# MUX_1_1.net
KiCad netlist of a schematic drawn in EAGLE
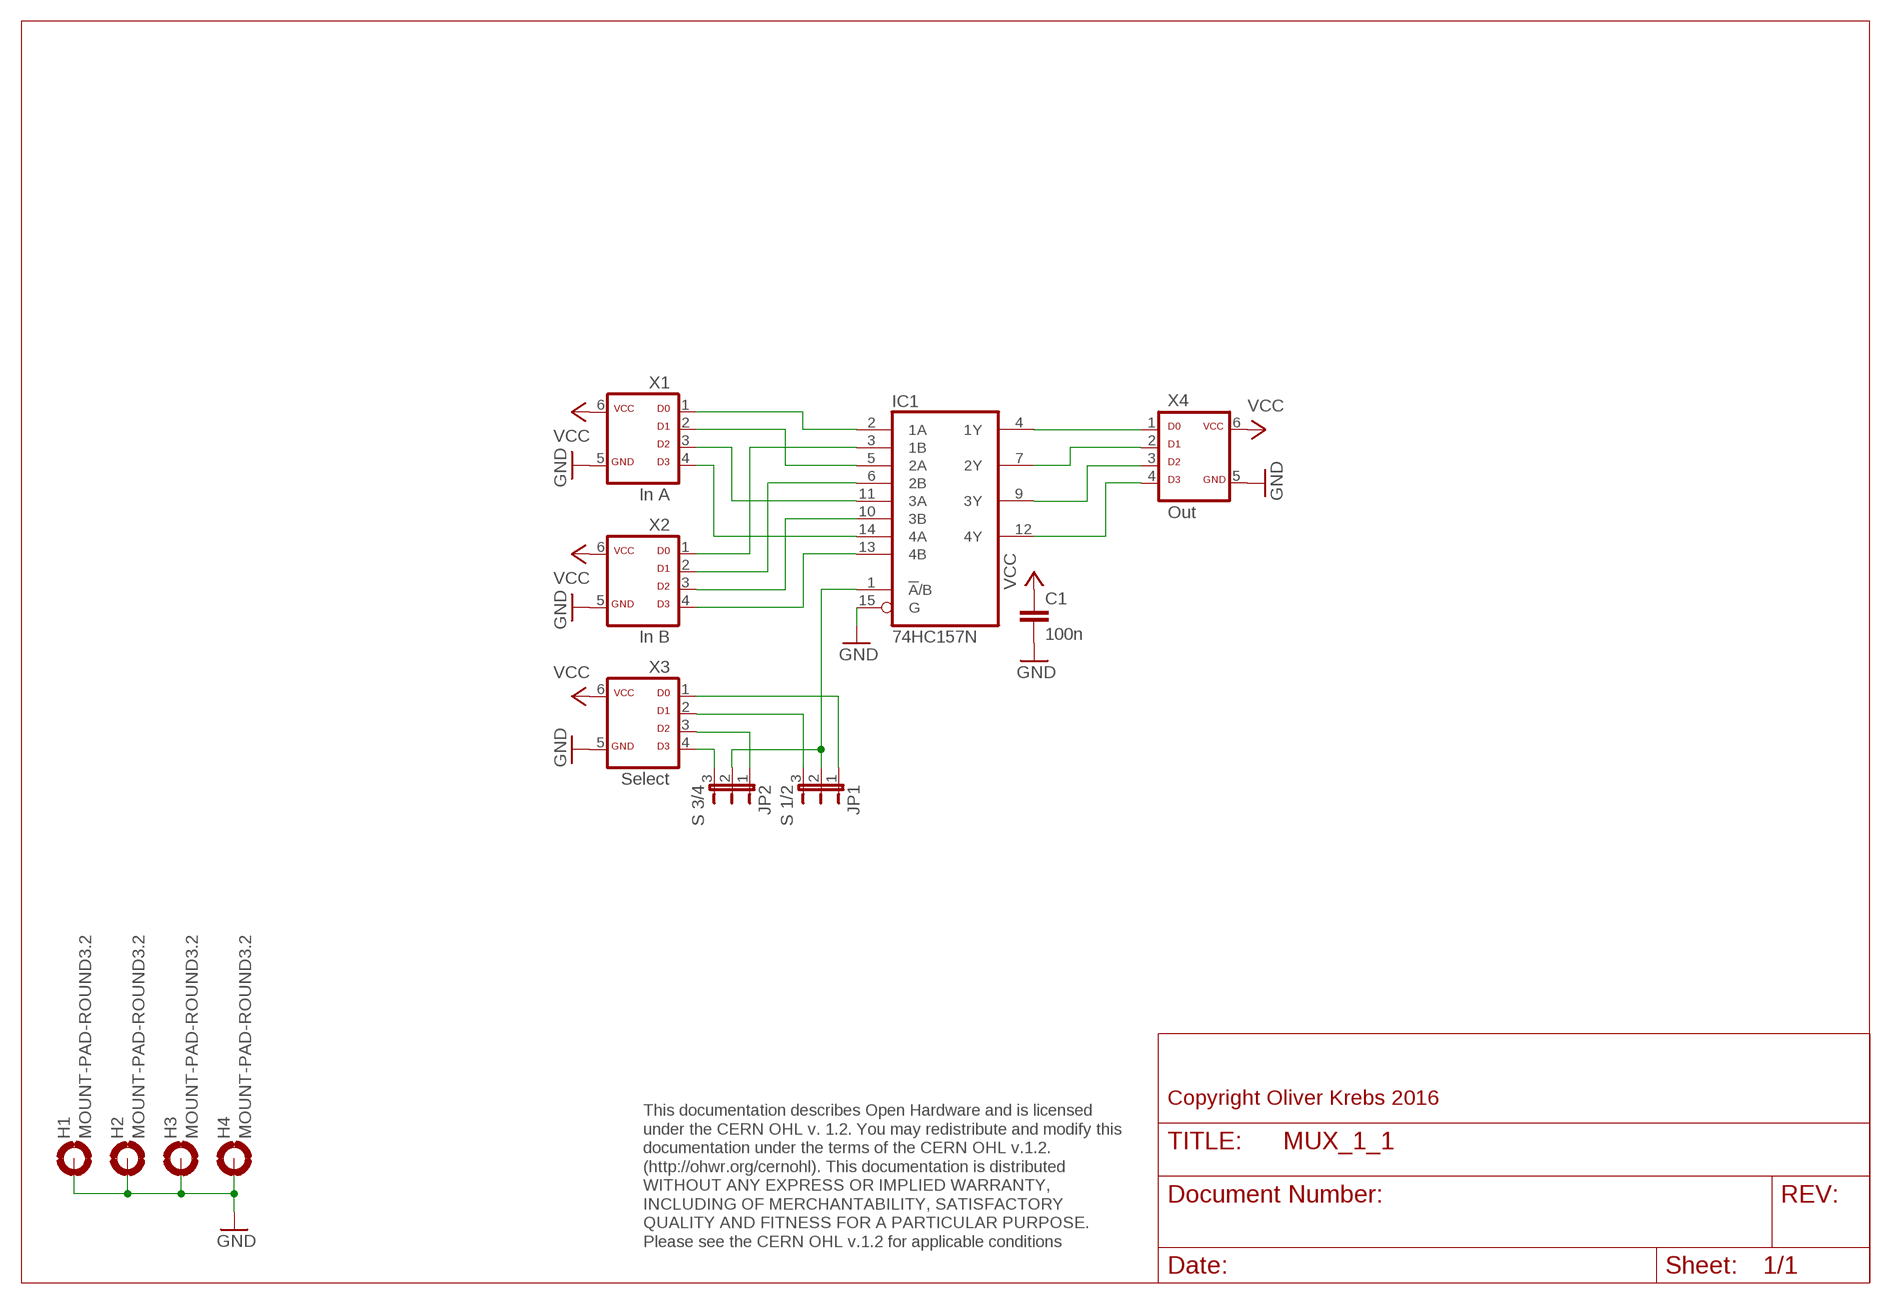
[diagram p0: schematic, sheet 1]

(export (version "E")
  (design (tool "Eeschema 10.0.6"))
  (components
    (comp (ref "C1")
      (value "100n")
      (footprint "eagle-import:C050-025X075")
      (libsource (lib "eagle-import") (part "C-EU050-025X075"))
    )
    (comp (ref "H1")
      (value "MOUNT-PAD-ROUND3.2")
      (footprint "eagle-import:3,2-PAD")
      (libsource (lib "eagle-import") (part "MOUNT-PAD-ROUND3.2"))
    )
    (comp (ref "H2")
      (value "MOUNT-PAD-ROUND3.2")
      (footprint "eagle-import:3,2-PAD")
      (libsource (lib "eagle-import") (part "MOUNT-PAD-ROUND3.2"))
    )
    (comp (ref "H3")
      (value "MOUNT-PAD-ROUND3.2")
      (footprint "eagle-import:3,2-PAD")
      (libsource (lib "eagle-import") (part "MOUNT-PAD-ROUND3.2"))
    )
    (comp (ref "H4")
      (value "MOUNT-PAD-ROUND3.2")
      (footprint "eagle-import:3,2-PAD")
      (libsource (lib "eagle-import") (part "MOUNT-PAD-ROUND3.2"))
    )
    (comp (ref "IC1")
      (value "74HC157N")
      (footprint "eagle-import:DIL16")
      (libsource (lib "eagle-import") (part "74157NHC"))
    )
    (comp (ref "JP1")
      (value "S 1/2")
      (footprint "eagle-import:JP2")
      (libsource (lib "eagle-import") (part "JP2E"))
    )
    (comp (ref "JP2")
      (value "S 3/4")
      (footprint "eagle-import:JP2")
      (libsource (lib "eagle-import") (part "JP2E"))
    )
    (comp (ref "X1")
      (value "In A")
      (footprint "eagle-import:ML-6")
      (libsource (lib "eagle-import") (part "ML6D"))
    )
    (comp (ref "X2")
      (value "In B")
      (footprint "eagle-import:ML-6")
      (libsource (lib "eagle-import") (part "ML6D"))
    )
    (comp (ref "X3")
      (value "Select")
      (footprint "eagle-import:ML-6")
      (libsource (lib "eagle-import") (part "ML6D"))
    )
    (comp (ref "X4")
      (value "Out")
      (footprint "eagle-import:ML-6")
      (libsource (lib "eagle-import") (part "ML6D"))
    )
  )
  (nets
    (net (code "1") (name "GND") (class "Default")
      (node (ref "C1") (pin "2") (pinfunction "2_2") (pintype "passive"))
      (node (ref "H1") (pin "B3,2") (pinfunction "MOUNT_B3,2") (pintype "passive"))
      (node (ref "H2") (pin "B3,2") (pinfunction "MOUNT_B3,2") (pintype "passive"))
      (node (ref "H3") (pin "B3,2") (pinfunction "MOUNT_B3,2") (pintype "passive"))
      (node (ref "H4") (pin "B3,2") (pinfunction "MOUNT_B3,2") (pintype "passive"))
      (node (ref "IC1") (pin "15") (pinfunction "G_15") (pintype "input"))
      (node (ref "X1") (pin "5") (pinfunction "5_5") (pintype "passive"))
      (node (ref "X2") (pin "5") (pinfunction "5_5") (pintype "passive"))
      (node (ref "X3") (pin "5") (pinfunction "5_5") (pintype "passive"))
      (node (ref "X4") (pin "5") (pinfunction "5_5") (pintype "passive"))
    )
    (net (code "2") (name "Net-(IC1A-1A)") (class "Default")
      (node (ref "IC1") (pin "2") (pinfunction "1A_2") (pintype "input"))
      (node (ref "X1") (pin "1") (pinfunction "1_1") (pintype "passive"))
    )
    (net (code "3") (name "Net-(IC1A-1B)") (class "Default")
      (node (ref "IC1") (pin "3") (pinfunction "1B_3") (pintype "input"))
      (node (ref "X2") (pin "1") (pinfunction "1_1") (pintype "passive"))
    )
    (net (code "4") (name "Net-(IC1A-1Y)") (class "Default")
      (node (ref "IC1") (pin "4") (pinfunction "1Y_4") (pintype "output"))
      (node (ref "X4") (pin "1") (pinfunction "1_1") (pintype "passive"))
    )
    (net (code "5") (name "Net-(IC1A-2A)") (class "Default")
      (node (ref "IC1") (pin "5") (pinfunction "2A_5") (pintype "input"))
      (node (ref "X1") (pin "2") (pinfunction "2_2") (pintype "passive"))
    )
    (net (code "6") (name "Net-(IC1A-2B)") (class "Default")
      (node (ref "IC1") (pin "6") (pinfunction "2B_6") (pintype "input"))
      (node (ref "X2") (pin "2") (pinfunction "2_2") (pintype "passive"))
    )
    (net (code "7") (name "Net-(IC1A-2Y)") (class "Default")
      (node (ref "IC1") (pin "7") (pinfunction "2Y_7") (pintype "output"))
      (node (ref "X4") (pin "2") (pinfunction "2_2") (pintype "passive"))
    )
    (net (code "8") (name "Net-(IC1A-3A)") (class "Default")
      (node (ref "IC1") (pin "11") (pinfunction "3A_11") (pintype "input"))
      (node (ref "X1") (pin "3") (pinfunction "3_3") (pintype "passive"))
    )
    (net (code "9") (name "Net-(IC1A-3B)") (class "Default")
      (node (ref "IC1") (pin "10") (pinfunction "3B_10") (pintype "input"))
      (node (ref "X2") (pin "3") (pinfunction "3_3") (pintype "passive"))
    )
    (net (code "10") (name "Net-(IC1A-3Y)") (class "Default")
      (node (ref "IC1") (pin "9") (pinfunction "3Y_9") (pintype "output"))
      (node (ref "X4") (pin "3") (pinfunction "3_3") (pintype "passive"))
    )
    (net (code "11") (name "Net-(IC1A-4A)") (class "Default")
      (node (ref "IC1") (pin "14") (pinfunction "4A_14") (pintype "input"))
      (node (ref "X1") (pin "4") (pinfunction "4_4") (pintype "passive"))
    )
    (net (code "12") (name "Net-(IC1A-4B)") (class "Default")
      (node (ref "IC1") (pin "13") (pinfunction "4B_13") (pintype "input"))
      (node (ref "X2") (pin "4") (pinfunction "4_4") (pintype "passive"))
    )
    (net (code "13") (name "Net-(IC1A-4Y)") (class "Default")
      (node (ref "IC1") (pin "12") (pinfunction "4Y_12") (pintype "output"))
      (node (ref "X4") (pin "4") (pinfunction "4_4") (pintype "passive"))
    )
    (net (code "14") (name "Net-(IC1A-~{A}{slash}B)") (class "Default")
      (node (ref "IC1") (pin "1") (pinfunction "~{A}/B_1") (pintype "input"))
      (node (ref "JP1") (pin "2") (pinfunction "2_2") (pintype "passive"))
      (node (ref "JP2") (pin "2") (pinfunction "2_2") (pintype "passive"))
    )
    (net (code "15") (name "Net-(JP1-Pad1)") (class "Default")
      (node (ref "JP1") (pin "1") (pinfunction "1_1") (pintype "passive"))
      (node (ref "X3") (pin "1") (pinfunction "1_1") (pintype "passive"))
    )
    (net (code "16") (name "Net-(JP1-Pad3)") (class "Default")
      (node (ref "JP1") (pin "3") (pinfunction "3_3") (pintype "passive"))
      (node (ref "X3") (pin "2") (pinfunction "2_2") (pintype "passive"))
    )
    (net (code "17") (name "Net-(JP2-Pad1)") (class "Default")
      (node (ref "JP2") (pin "1") (pinfunction "1_1") (pintype "passive"))
      (node (ref "X3") (pin "3") (pinfunction "3_3") (pintype "passive"))
    )
    (net (code "18") (name "Net-(JP2-Pad3)") (class "Default")
      (node (ref "JP2") (pin "3") (pinfunction "3_3") (pintype "passive"))
      (node (ref "X3") (pin "4") (pinfunction "4_4") (pintype "passive"))
    )
    (net (code "19") (name "VCC") (class "Default")
      (node (ref "C1") (pin "1") (pinfunction "1_1") (pintype "passive"))
      (node (ref "X1") (pin "6") (pinfunction "6_6") (pintype "passive"))
      (node (ref "X2") (pin "6") (pinfunction "6_6") (pintype "passive"))
      (node (ref "X3") (pin "6") (pinfunction "6_6") (pintype "passive"))
      (node (ref "X4") (pin "6") (pinfunction "6_6") (pintype "passive"))
    )
  )
)
